# USB2-C-INTERFACE-EMI-ESD.net
KiCad netlist of a schematic drawn in Altium Designer
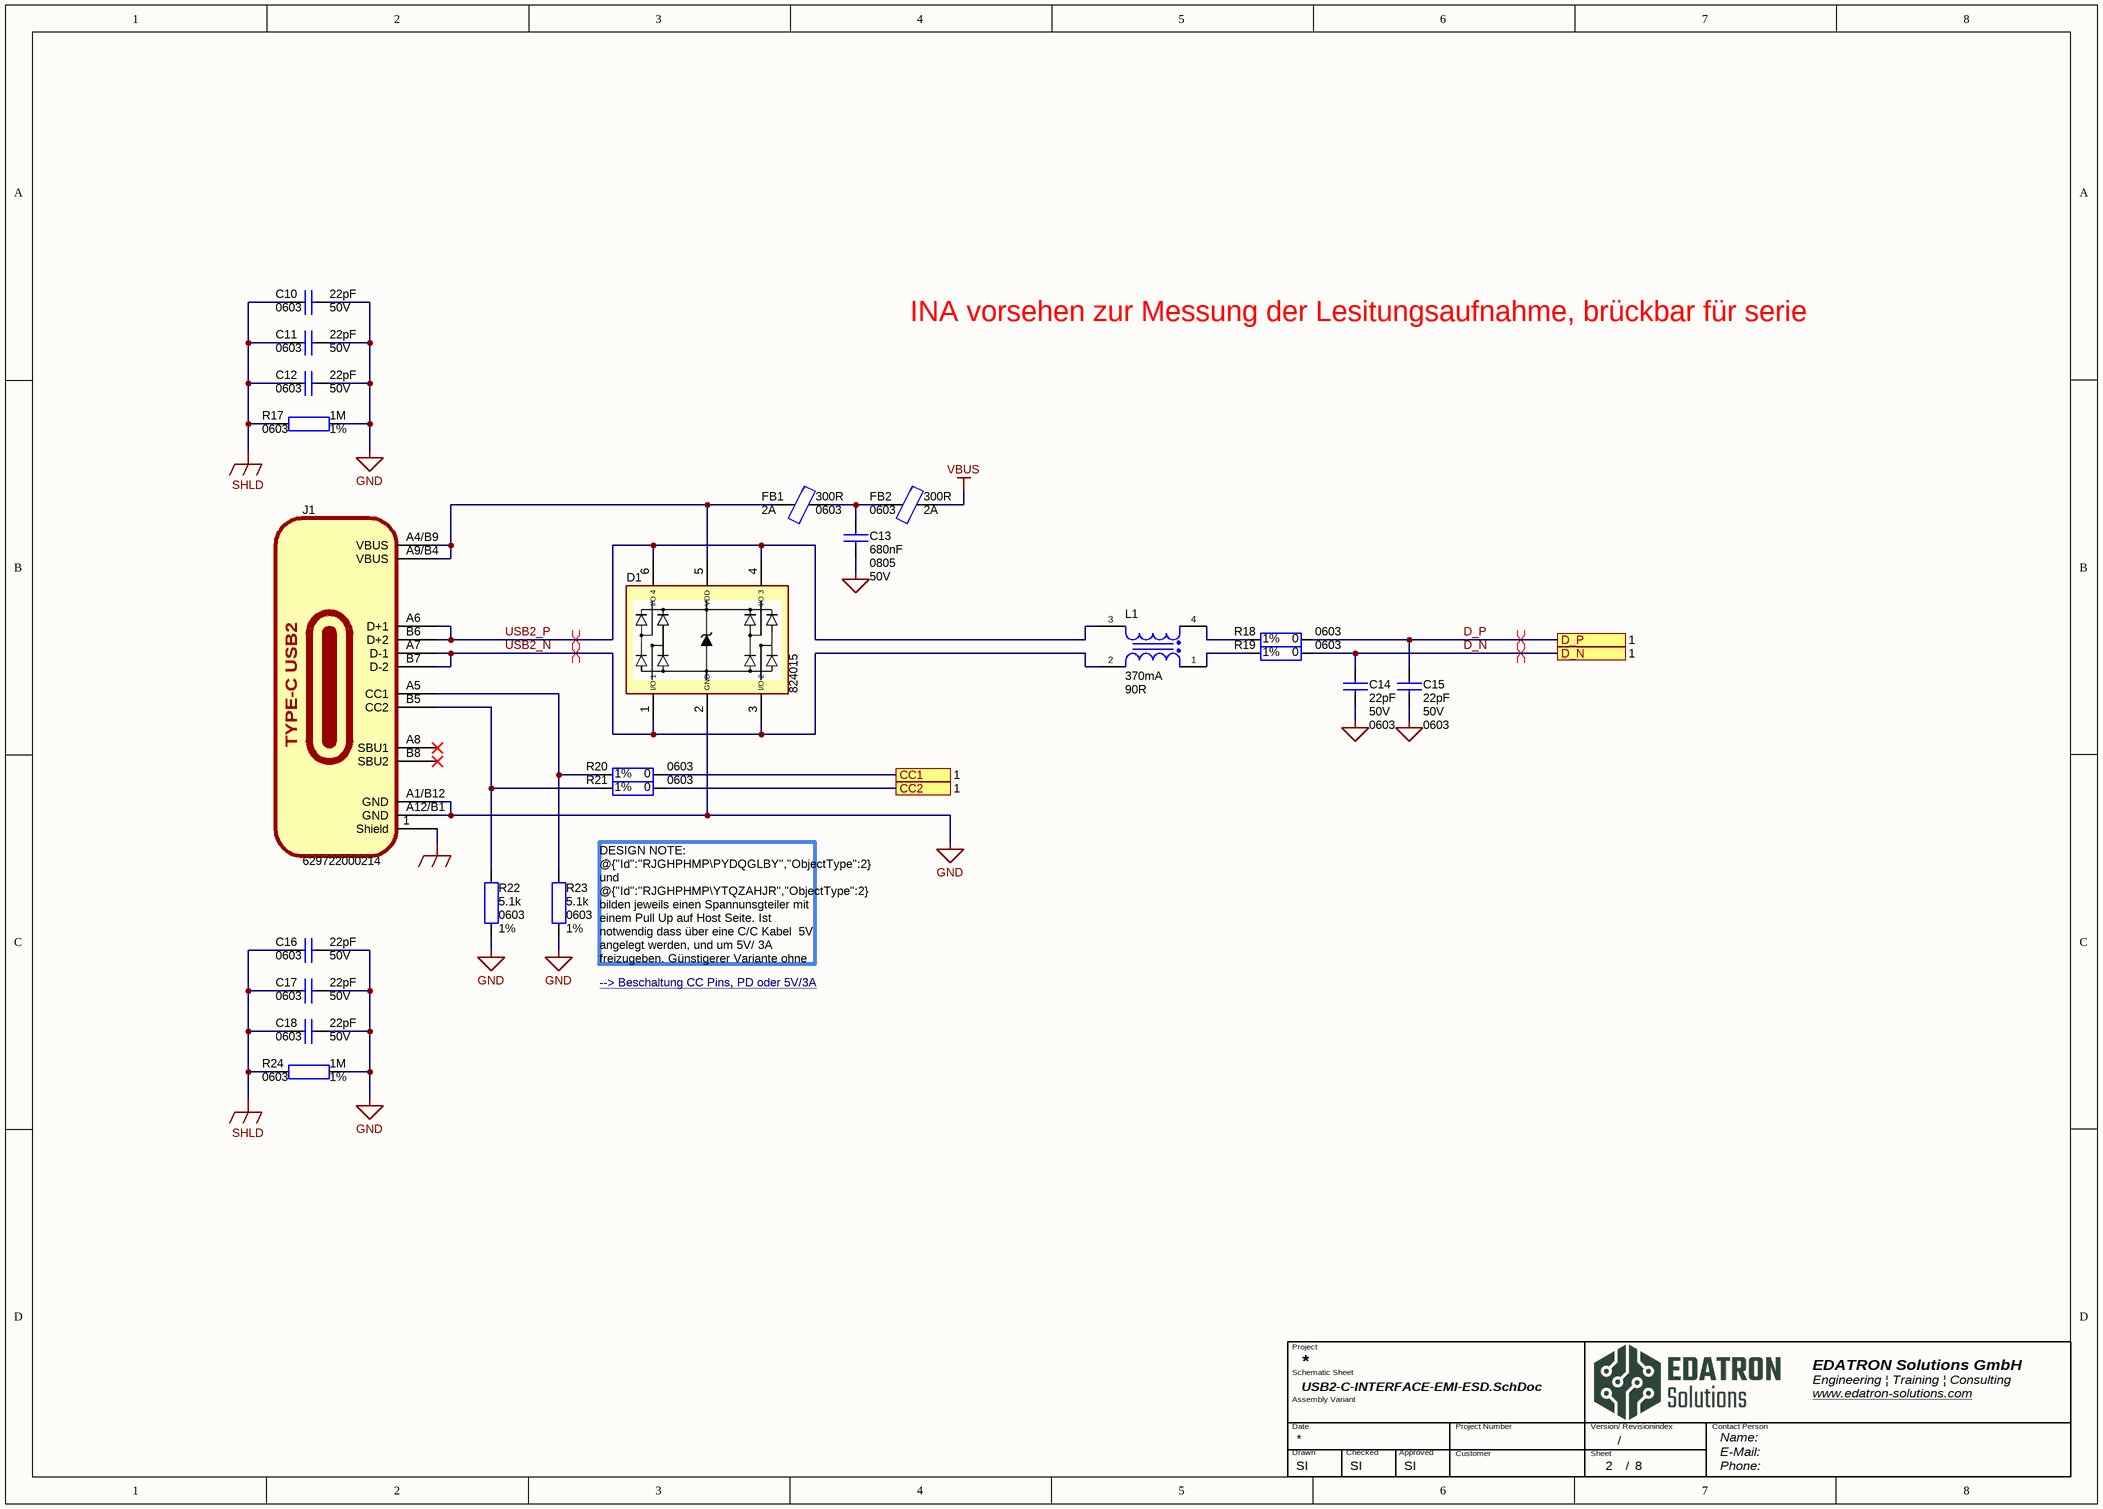
[diagram p0: USB2-C-INTERFACE-EMI-ESD.SchDoc]

(export (version "E")
  (design (tool "Eeschema 10.0.6"))
  (components
    (comp (ref "C10")
      (value "22pF")
      (footprint "CAPC0603X37L")
      (description "CAPACITOR 22 pF 0603 X7R 50V 10%")
      (fields
        (field (name "VOLTAGE") "50V")
        (field (name "MANUFACTURER 1 PART NUMBER") "C0603C220K5RACTU")
        (field (name "CASE/PACKAGE") "0603")
        (field (name "TOLERANCE") "10%")
        (field (name "COMMENT DESIGNER") "can be substituted same values other manufacturer")
      )
      (libsource (lib "EDATRON Solutions GmbH") (part "C"))
    )
    (comp (ref "C11")
      (value "22pF")
      (footprint "CAPC0603X37L")
      (description "CAPACITOR 22 pF 0603 X7R 50V 10%")
      (fields
        (field (name "VOLTAGE") "50V")
        (field (name "MANUFACTURER 1 PART NUMBER") "C0603C220K5RACTU")
        (field (name "CASE/PACKAGE") "0603")
        (field (name "TOLERANCE") "10%")
        (field (name "COMMENT DESIGNER") "can be substituted same values other manufacturer")
      )
      (libsource (lib "EDATRON Solutions GmbH") (part "C"))
    )
    (comp (ref "C12")
      (value "22pF")
      (footprint "CAPC0603X37L")
      (description "CAPACITOR 22 pF 0603 X7R 50V 10%")
      (fields
        (field (name "VOLTAGE") "50V")
        (field (name "MANUFACTURER 1 PART NUMBER") "C0603C220K5RACTU")
        (field (name "CASE/PACKAGE") "0603")
        (field (name "TOLERANCE") "10%")
        (field (name "COMMENT DESIGNER") "can be substituted same values other manufacturer")
      )
      (libsource (lib "EDATRON Solutions GmbH") (part "C"))
    )
    (comp (ref "C13")
      (value "680nF")
      (footprint "CAPC0805X57L")
      (description "CAPACITOR 680 nF 0805 X7R 50V 10%")
      (fields
        (field (name "TOLERANCE") "10%")
        (field (name "CASE/PACKAGE") "0805")
        (field (name "VOLTAGE") "50V")
        (field (name "MANUFACTURER 1 PART NUMBER") "C0805C684K5RACTU")
        (field (name "COMMENT DESIGNER") "can be substituted same values other manufacturer")
      )
      (libsource (lib "EDATRON Solutions GmbH") (part "C"))
    )
    (comp (ref "C14")
      (value "22pF")
      (footprint "CAPC0603X37L")
      (description "CAPACITOR 22 pF 0603 X7R 50V 10%")
      (fields
        (field (name "VOLTAGE") "50V")
        (field (name "MANUFACTURER 1 PART NUMBER") "C0603C220K5RACTU")
        (field (name "CASE/PACKAGE") "0603")
        (field (name "TOLERANCE") "10%")
        (field (name "COMMENT DESIGNER") "can be substituted same values other manufacturer")
      )
      (libsource (lib "EDATRON Solutions GmbH") (part "C"))
    )
    (comp (ref "C15")
      (value "22pF")
      (footprint "CAPC0603X37L")
      (description "CAPACITOR 22 pF 0603 X7R 50V 10%")
      (fields
        (field (name "VOLTAGE") "50V")
        (field (name "MANUFACTURER 1 PART NUMBER") "C0603C220K5RACTU")
        (field (name "CASE/PACKAGE") "0603")
        (field (name "TOLERANCE") "10%")
        (field (name "COMMENT DESIGNER") "can be substituted same values other manufacturer")
      )
      (libsource (lib "EDATRON Solutions GmbH") (part "C"))
    )
    (comp (ref "C16")
      (value "22pF")
      (footprint "CAPC0603X37L")
      (description "CAPACITOR 22 pF 0603 X7R 50V 10%")
      (fields
        (field (name "VOLTAGE") "50V")
        (field (name "MANUFACTURER 1 PART NUMBER") "C0603C220K5RACTU")
        (field (name "CASE/PACKAGE") "0603")
        (field (name "TOLERANCE") "10%")
        (field (name "COMMENT DESIGNER") "can be substituted same values other manufacturer")
      )
      (libsource (lib "EDATRON Solutions GmbH") (part "C"))
    )
    (comp (ref "C17")
      (value "22pF")
      (footprint "CAPC0603X37L")
      (description "CAPACITOR 22 pF 0603 X7R 50V 10%")
      (fields
        (field (name "VOLTAGE") "50V")
        (field (name "MANUFACTURER 1 PART NUMBER") "C0603C220K5RACTU")
        (field (name "CASE/PACKAGE") "0603")
        (field (name "TOLERANCE") "10%")
        (field (name "COMMENT DESIGNER") "can be substituted same values other manufacturer")
      )
      (libsource (lib "EDATRON Solutions GmbH") (part "C"))
    )
    (comp (ref "C18")
      (value "22pF")
      (footprint "CAPC0603X37L")
      (description "CAPACITOR 22 pF 0603 X7R 50V 10%")
      (fields
        (field (name "VOLTAGE") "50V")
        (field (name "MANUFACTURER 1 PART NUMBER") "C0603C220K5RACTU")
        (field (name "CASE/PACKAGE") "0603")
        (field (name "TOLERANCE") "10%")
        (field (name "COMMENT DESIGNER") "can be substituted same values other manufacturer")
      )
      (libsource (lib "EDATRON Solutions GmbH") (part "C"))
    )
    (comp (ref "D1")
      (value "824015")
      (footprint "SOT23-6L")
      (description "Trans Voltage Suppressor Diode, 5V V(RWM), Unidirectional, 1 Element, Silicon")
      (fields (field (name "VOLTAGE") "5V"))
      (libsource (lib "EDATRON Solutions GmbH") (part "824015"))
    )
    (comp (ref "FB1")
      (value "300R")
      (footprint "BEADC0603X39L")
      (description "EMI Suppression Ferrite Bead")
      (fields
        (field (name "RATED CURRENT") "2A")
        (field (name "CASE/PACKAGE") "0603")
        (field (name "TOLERANCE") "25%")
        (field (name "MANUFACTURER 1 PART NUMBER") "742792641")
      )
      (libsource (lib "EDATRON Solutions GmbH") (part "FB"))
    )
    (comp (ref "FB2")
      (value "300R")
      (footprint "BEADC0603X39L")
      (description "EMI Suppression Ferrite Bead")
      (fields
        (field (name "RATED CURRENT") "2A")
        (field (name "CASE/PACKAGE") "0603")
        (field (name "TOLERANCE") "25%")
        (field (name "MANUFACTURER 1 PART NUMBER") "742792641")
      )
      (libsource (lib "EDATRON Solutions GmbH") (part "FB"))
    )
    (comp (ref "J1")
      (value "629722000214")
      (footprint "WR-COM USB 2.0_Type C_Horizontal_SMT")
      (description "USB 2.0_Type C_Horizontal_SMT")
      (libsource (lib "EDATRON Solutions GmbH") (part "629722000214"))
    )
    (comp (ref "L1")
      (value "90R")
      (footprint "744231091-Footprint-1")
      (description "WE-CNSW SMT Common Mode Line Filter, 0805")
      (fields
        (field (name "MANUFACTURER 1 PART NUMBER") "744231091")
        (field (name "RATED CURRENT") "370mA")
        (field (name "VOLTAGE") "50V")
      )
      (libsource (lib "EDATRON Solutions GmbH") (part "CMC"))
    )
    (comp (ref "R17")
      (value "1M")
      (footprint "RESC0603X21L")
      (description "RESISTOR 1M 1% 0603 100mW")
      (fields
        (field (name "MANUFACTURER 1 PART NUMBER") "RC0603FR-071ML")
        (field (name "POWER") "100mW")
        (field (name "TOLERANCE") "1%")
        (field (name "CASE/PACKAGE") "0603")
        (field (name "COMMENT DESIGNER") "can be substituted same values other manufacturers")
      )
      (libsource (lib "EDATRON Solutions GmbH") (part "R"))
    )
    (comp (ref "R18")
      (value "0")
      (footprint "RESC0603X21L")
      (description "RESISTOR 0R 1% 0603 100mW")
      (fields
        (field (name "MANUFACTURER 1 PART NUMBER") "RC0603FR-070RL")
        (field (name "CASE/PACKAGE") "0603")
        (field (name "POWER") "100mW")
        (field (name "TOLERANCE") "1%")
        (field (name "COMMENT DESIGNER") "can be substituted same values other manufacturers")
      )
      (libsource (lib "EDATRON Solutions GmbH") (part "R"))
    )
    (comp (ref "R19")
      (value "0")
      (footprint "RESC0603X21L")
      (description "RESISTOR 0R 1% 0603 100mW")
      (fields
        (field (name "MANUFACTURER 1 PART NUMBER") "RC0603FR-070RL")
        (field (name "CASE/PACKAGE") "0603")
        (field (name "POWER") "100mW")
        (field (name "TOLERANCE") "1%")
        (field (name "COMMENT DESIGNER") "can be substituted same values other manufacturers")
      )
      (libsource (lib "EDATRON Solutions GmbH") (part "R"))
    )
    (comp (ref "R20")
      (value "0")
      (footprint "RESC0603X21L")
      (description "RESISTOR 0R 1% 0603 100mW")
      (fields
        (field (name "MANUFACTURER 1 PART NUMBER") "RC0603FR-070RL")
        (field (name "CASE/PACKAGE") "0603")
        (field (name "POWER") "100mW")
        (field (name "TOLERANCE") "1%")
        (field (name "COMMENT DESIGNER") "can be substituted same values other manufacturers")
      )
      (libsource (lib "EDATRON Solutions GmbH") (part "R"))
    )
    (comp (ref "R21")
      (value "0")
      (footprint "RESC0603X21L")
      (description "RESISTOR 0R 1% 0603 100mW")
      (fields
        (field (name "MANUFACTURER 1 PART NUMBER") "RC0603FR-070RL")
        (field (name "CASE/PACKAGE") "0603")
        (field (name "POWER") "100mW")
        (field (name "TOLERANCE") "1%")
        (field (name "COMMENT DESIGNER") "can be substituted same values other manufacturers")
      )
      (libsource (lib "EDATRON Solutions GmbH") (part "R"))
    )
    (comp (ref "R22")
      (value "5.1k")
      (footprint "RESC0603X21L")
      (description "RESISTOR 5K1 1% 0603 100mW")
      (fields
        (field (name "CASE/PACKAGE") "0603")
        (field (name "POWER") "100mW")
        (field (name "TOLERANCE") "1%")
        (field (name "MANUFACTURER 1 PART NUMBER") "RC0603FR-075K1L")
        (field (name "COMMENT DESIGNER") "can be substituted same values other manufacturers")
      )
      (libsource (lib "") (part "R_1"))
    )
    (comp (ref "R23")
      (value "5.1k")
      (footprint "RESC0603X21L")
      (description "RESISTOR 5K1 1% 0603 100mW")
      (fields
        (field (name "CASE/PACKAGE") "0603")
        (field (name "POWER") "100mW")
        (field (name "TOLERANCE") "1%")
        (field (name "MANUFACTURER 1 PART NUMBER") "RC0603FR-075K1L")
        (field (name "COMMENT DESIGNER") "can be substituted same values other manufacturers")
      )
      (libsource (lib "") (part "R_1"))
    )
    (comp (ref "R24")
      (value "1M")
      (footprint "RESC0603X21L")
      (description "RESISTOR 1M 1% 0603 100mW")
      (fields
        (field (name "MANUFACTURER 1 PART NUMBER") "RC0603FR-071ML")
        (field (name "POWER") "100mW")
        (field (name "TOLERANCE") "1%")
        (field (name "CASE/PACKAGE") "0603")
        (field (name "COMMENT DESIGNER") "can be substituted same values other manufacturers")
      )
      (libsource (lib "EDATRON Solutions GmbH") (part "R"))
    )
  )
  (nets
    (net (code "1") (name "/CC1") (class "Default")
      (node (ref "R20") (pin "2") (pinfunction "2_2") (pintype "passive"))
    )
    (net (code "2") (name "/CC2") (class "Default")
      (node (ref "R21") (pin "2") (pinfunction "2_2") (pintype "passive"))
    )
    (net (code "3") (name "/D_N") (class "Default")
      (node (ref "C14") (pin "1") (pinfunction "1_1") (pintype "passive"))
      (node (ref "R19") (pin "2") (pinfunction "2_2") (pintype "passive"))
    )
    (net (code "4") (name "/D_P") (class "Default")
      (node (ref "C15") (pin "1") (pinfunction "1_1") (pintype "passive"))
      (node (ref "R18") (pin "2") (pinfunction "2_2") (pintype "passive"))
    )
    (net (code "5") (name "/USB2_N") (class "Default")
      (node (ref "D1") (pin "1") (pinfunction "I/O_1_1") (pintype "passive"))
      (node (ref "D1") (pin "3") (pinfunction "I/O_2_3") (pintype "power_in"))
      (node (ref "J1") (pin "A7") (pinfunction "D-1_A7") (pintype "passive"))
      (node (ref "J1") (pin "B7") (pinfunction "D-2_B7") (pintype "passive"))
      (node (ref "L1") (pin "2") (pinfunction "2_2") (pintype "passive"))
    )
    (net (code "6") (name "/USB2_P") (class "Default")
      (node (ref "D1") (pin "4") (pinfunction "I/O_3_4") (pintype "passive"))
      (node (ref "D1") (pin "6") (pinfunction "I/O_4_6") (pintype "power_in"))
      (node (ref "J1") (pin "A6") (pinfunction "D+1_A6") (pintype "passive"))
      (node (ref "J1") (pin "B6") (pinfunction "D+2_B6") (pintype "passive"))
      (node (ref "L1") (pin "3") (pinfunction "3_3") (pintype "passive"))
    )
    (net (code "7") (name "GND") (class "Default")
      (node (ref "C10") (pin "2") (pinfunction "2_2") (pintype "passive"))
      (node (ref "C11") (pin "2") (pinfunction "2_2") (pintype "passive"))
      (node (ref "C12") (pin "2") (pinfunction "2_2") (pintype "passive"))
      (node (ref "C13") (pin "2") (pinfunction "2_2") (pintype "passive"))
      (node (ref "C14") (pin "2") (pinfunction "2_2") (pintype "passive"))
      (node (ref "C15") (pin "2") (pinfunction "2_2") (pintype "passive"))
      (node (ref "C16") (pin "2") (pinfunction "2_2") (pintype "passive"))
      (node (ref "C17") (pin "2") (pinfunction "2_2") (pintype "passive"))
      (node (ref "C18") (pin "2") (pinfunction "2_2") (pintype "passive"))
      (node (ref "D1") (pin "2") (pinfunction "GND_2") (pintype "passive"))
      (node (ref "J1") (pin "A1/B12") (pinfunction "GND_A1/B12") (pintype "passive"))
      (node (ref "J1") (pin "A12/B1") (pinfunction "GND_A12/B1") (pintype "passive"))
      (node (ref "R17") (pin "2") (pinfunction "2_2") (pintype "passive"))
      (node (ref "R22") (pin "2") (pinfunction "2_2") (pintype "passive"))
      (node (ref "R23") (pin "2") (pinfunction "2_2") (pintype "passive"))
      (node (ref "R24") (pin "2") (pinfunction "2_2") (pintype "passive"))
    )
    (net (code "8") (name "Net-(C13-Pad1)") (class "Default")
      (node (ref "C13") (pin "1") (pinfunction "1_1") (pintype "passive"))
      (node (ref "FB1") (pin "2") (pinfunction "2_2") (pintype "passive"))
      (node (ref "FB2") (pin "1") (pinfunction "1_1") (pintype "passive"))
    )
    (net (code "9") (name "Net-(D1-VDD)") (class "Default")
      (node (ref "D1") (pin "5") (pinfunction "VDD_5") (pintype "passive"))
      (node (ref "FB1") (pin "1") (pinfunction "1_1") (pintype "passive"))
      (node (ref "J1") (pin "A4/B9") (pinfunction "VBUS_A4/B9") (pintype "passive"))
      (node (ref "J1") (pin "A9/B4") (pinfunction "VBUS_A9/B4") (pintype "passive"))
    )
    (net (code "10") (name "Net-(J1-CC1)") (class "Default")
      (node (ref "J1") (pin "A5") (pinfunction "CC1_A5") (pintype "passive"))
      (node (ref "R20") (pin "1") (pinfunction "1_1") (pintype "passive"))
      (node (ref "R23") (pin "1") (pinfunction "1_1") (pintype "passive"))
    )
    (net (code "11") (name "Net-(J1-CC2)") (class "Default")
      (node (ref "J1") (pin "B5") (pinfunction "CC2_B5") (pintype "passive"))
      (node (ref "R21") (pin "1") (pinfunction "1_1") (pintype "passive"))
      (node (ref "R22") (pin "1") (pinfunction "1_1") (pintype "passive"))
    )
    (net (code "12") (name "Net-(L1-Pad1)") (class "Default")
      (node (ref "L1") (pin "1") (pinfunction "1_1") (pintype "passive"))
      (node (ref "R19") (pin "1") (pinfunction "1_1") (pintype "passive"))
    )
    (net (code "13") (name "Net-(L1-Pad4)") (class "Default")
      (node (ref "L1") (pin "4") (pinfunction "4_4") (pintype "passive"))
      (node (ref "R18") (pin "1") (pinfunction "1_1") (pintype "passive"))
    )
    (net (code "14") (name "SHLD") (class "Default")
      (node (ref "C10") (pin "1") (pinfunction "1_1") (pintype "passive"))
      (node (ref "C11") (pin "1") (pinfunction "1_1") (pintype "passive"))
      (node (ref "C12") (pin "1") (pinfunction "1_1") (pintype "passive"))
      (node (ref "C16") (pin "1") (pinfunction "1_1") (pintype "passive"))
      (node (ref "C17") (pin "1") (pinfunction "1_1") (pintype "passive"))
      (node (ref "C18") (pin "1") (pinfunction "1_1") (pintype "passive"))
      (node (ref "J1") (pin "1") (pinfunction "Shield_1") (pintype "passive"))
      (node (ref "R17") (pin "1") (pinfunction "1_1") (pintype "passive"))
      (node (ref "R24") (pin "1") (pinfunction "1_1") (pintype "passive"))
    )
    (net (code "15") (name "VBUS") (class "Default")
      (node (ref "FB2") (pin "2") (pinfunction "2_2") (pintype "passive"))
    )
    (net (code "16") (name "unconnected-(J1-SBU1-PadA8)") (class "Default")
      (node (ref "J1") (pin "A8") (pinfunction "SBU1_A8") (pintype "passive+no_connect"))
    )
    (net (code "17") (name "unconnected-(J1-SBU2-PadB8)") (class "Default")
      (node (ref "J1") (pin "B8") (pinfunction "SBU2_B8") (pintype "passive+no_connect"))
    )
  )
)
